# AINx2.net
KiCad netlist of a schematic drawn in EAGLE
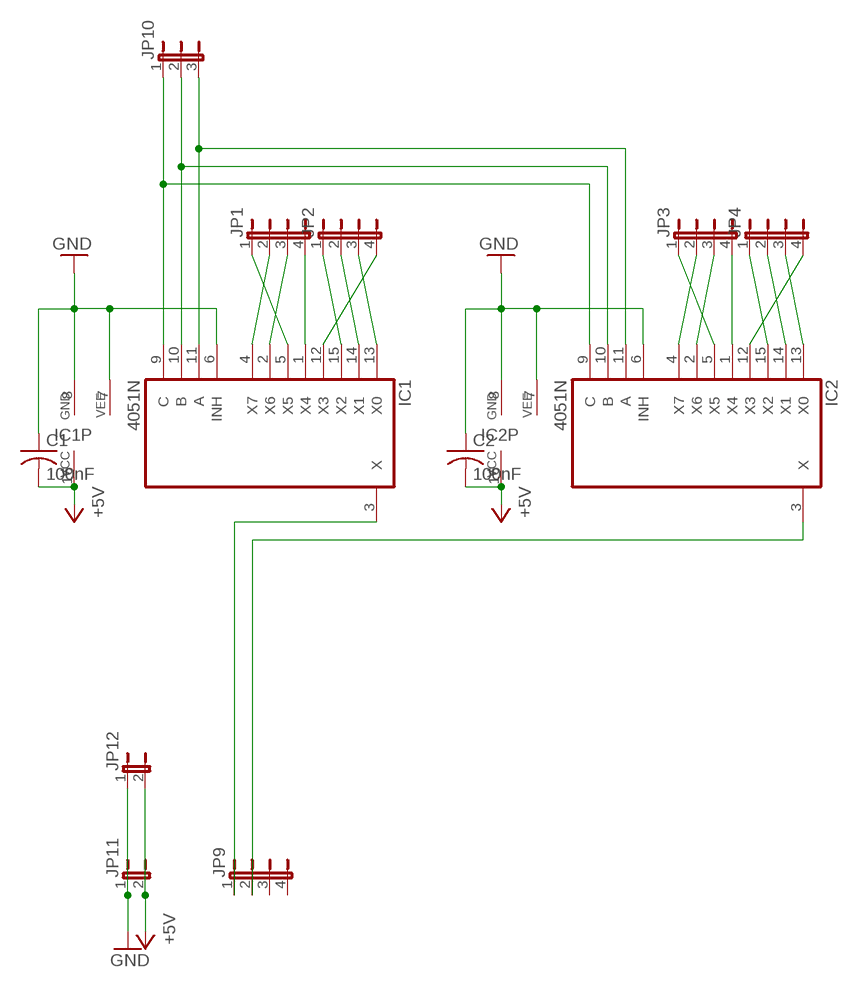
[diagram p0: schematic, sheet 1]

(export (version "E")
  (design (tool "Eeschema 10.0.6"))
  (components
    (comp (ref "C1")
      (value "100nF")
      (footprint "eagle-import:C025-025X050")
      (libsource (lib "eagle-import") (part "C-US025-025X050"))
    )
    (comp (ref "C2")
      (value "100nF")
      (footprint "eagle-import:C025-025X050")
      (libsource (lib "eagle-import") (part "C-US025-025X050"))
    )
    (comp (ref "IC1")
      (value "4051N")
      (footprint "eagle-import:DIL16")
      (libsource (lib "eagle-import") (part "4051N"))
    )
    (comp (ref "IC2")
      (value "4051N")
      (footprint "eagle-import:DIL16")
      (libsource (lib "eagle-import") (part "4051N"))
    )
    (comp (ref "JP1")
      (value "JP4E")
      (footprint "eagle-import:JP4")
      (libsource (lib "eagle-import") (part "JP4E"))
    )
    (comp (ref "JP2")
      (value "JP4E")
      (footprint "eagle-import:JP4")
      (libsource (lib "eagle-import") (part "JP4E"))
    )
    (comp (ref "JP3")
      (value "JP4E")
      (footprint "eagle-import:JP4")
      (libsource (lib "eagle-import") (part "JP4E"))
    )
    (comp (ref "JP4")
      (value "JP4E")
      (footprint "eagle-import:JP4")
      (libsource (lib "eagle-import") (part "JP4E"))
    )
    (comp (ref "JP9")
      (value "JP4E")
      (footprint "eagle-import:JP4")
      (libsource (lib "eagle-import") (part "JP4E"))
    )
    (comp (ref "JP10")
      (value "JP2E")
      (footprint "eagle-import:JP2")
      (libsource (lib "eagle-import") (part "JP2E"))
    )
    (comp (ref "JP11")
      (value "JP1E")
      (footprint "eagle-import:JP1")
      (libsource (lib "eagle-import") (part "JP1E"))
    )
    (comp (ref "JP12")
      (value "JP1E")
      (footprint "eagle-import:JP1")
      (libsource (lib "eagle-import") (part "JP1E"))
    )
  )
  (nets
    (net (code "1") (name "+5V") (class "Default")
      (node (ref "C1") (pin "2") (pinfunction "2_2") (pintype "passive"))
      (node (ref "C2") (pin "2") (pinfunction "2_2") (pintype "passive"))
      (node (ref "IC1") (pin "16") (pinfunction "VCC_16") (pintype "power_in"))
      (node (ref "IC2") (pin "16") (pinfunction "VCC_16") (pintype "power_in"))
      (node (ref "JP11") (pin "2") (pinfunction "2_2") (pintype "passive"))
      (node (ref "JP12") (pin "2") (pinfunction "2_2") (pintype "passive"))
    )
    (net (code "2") (name "GND") (class "Default")
      (node (ref "C1") (pin "1") (pinfunction "1_1") (pintype "passive"))
      (node (ref "C2") (pin "1") (pinfunction "1_1") (pintype "passive"))
      (node (ref "IC1") (pin "6") (pinfunction "INH_6") (pintype "input"))
      (node (ref "IC1") (pin "7") (pinfunction "VEE_7") (pintype "power_in"))
      (node (ref "IC1") (pin "8") (pinfunction "GND_8") (pintype "power_in"))
      (node (ref "IC2") (pin "6") (pinfunction "INH_6") (pintype "input"))
      (node (ref "IC2") (pin "7") (pinfunction "VEE_7") (pintype "power_in"))
      (node (ref "IC2") (pin "8") (pinfunction "GND_8") (pintype "power_in"))
      (node (ref "JP11") (pin "1") (pinfunction "1_1") (pintype "passive"))
      (node (ref "JP12") (pin "1") (pinfunction "1_1") (pintype "passive"))
    )
    (net (code "3") (name "Net-(IC1A-A)") (class "Default")
      (node (ref "IC1") (pin "11") (pinfunction "A_11") (pintype "input"))
      (node (ref "IC2") (pin "11") (pinfunction "A_11") (pintype "input"))
      (node (ref "JP10") (pin "3") (pinfunction "3_3") (pintype "passive"))
    )
    (net (code "4") (name "Net-(IC1A-B)") (class "Default")
      (node (ref "IC1") (pin "10") (pinfunction "B_10") (pintype "input"))
      (node (ref "IC2") (pin "10") (pinfunction "B_10") (pintype "input"))
      (node (ref "JP10") (pin "2") (pinfunction "2_2") (pintype "passive"))
    )
    (net (code "5") (name "Net-(IC1A-C)") (class "Default")
      (node (ref "IC1") (pin "9") (pinfunction "C_9") (pintype "input"))
      (node (ref "IC2") (pin "9") (pinfunction "C_9") (pintype "input"))
      (node (ref "JP10") (pin "1") (pinfunction "1_1") (pintype "passive"))
    )
    (net (code "6") (name "Net-(IC1A-X)") (class "Default")
      (node (ref "IC1") (pin "3") (pinfunction "X_3") (pintype "bidirectional"))
      (node (ref "JP9") (pin "1") (pinfunction "1_1") (pintype "passive"))
    )
    (net (code "7") (name "Net-(IC1A-X0)") (class "Default")
      (node (ref "IC1") (pin "13") (pinfunction "X0_13") (pintype "bidirectional"))
      (node (ref "JP2") (pin "3") (pinfunction "3_3") (pintype "passive"))
    )
    (net (code "8") (name "Net-(IC1A-X1)") (class "Default")
      (node (ref "IC1") (pin "14") (pinfunction "X1_14") (pintype "bidirectional"))
      (node (ref "JP2") (pin "2") (pinfunction "2_2") (pintype "passive"))
    )
    (net (code "9") (name "Net-(IC1A-X2)") (class "Default")
      (node (ref "IC1") (pin "15") (pinfunction "X2_15") (pintype "bidirectional"))
      (node (ref "JP2") (pin "1") (pinfunction "1_1") (pintype "passive"))
    )
    (net (code "10") (name "Net-(IC1A-X3)") (class "Default")
      (node (ref "IC1") (pin "12") (pinfunction "X3_12") (pintype "bidirectional"))
      (node (ref "JP2") (pin "4") (pinfunction "4_4") (pintype "passive"))
    )
    (net (code "11") (name "Net-(IC1A-X4)") (class "Default")
      (node (ref "IC1") (pin "1") (pinfunction "X4_1") (pintype "bidirectional"))
      (node (ref "JP1") (pin "4") (pinfunction "4_4") (pintype "passive"))
    )
    (net (code "12") (name "Net-(IC1A-X5)") (class "Default")
      (node (ref "IC1") (pin "5") (pinfunction "X5_5") (pintype "bidirectional"))
      (node (ref "JP1") (pin "1") (pinfunction "1_1") (pintype "passive"))
    )
    (net (code "13") (name "Net-(IC1A-X6)") (class "Default")
      (node (ref "IC1") (pin "2") (pinfunction "X6_2") (pintype "bidirectional"))
      (node (ref "JP1") (pin "3") (pinfunction "3_3") (pintype "passive"))
    )
    (net (code "14") (name "Net-(IC1A-X7)") (class "Default")
      (node (ref "IC1") (pin "4") (pinfunction "X7_4") (pintype "bidirectional"))
      (node (ref "JP1") (pin "2") (pinfunction "2_2") (pintype "passive"))
    )
    (net (code "15") (name "Net-(IC2A-X)") (class "Default")
      (node (ref "IC2") (pin "3") (pinfunction "X_3") (pintype "bidirectional"))
      (node (ref "JP9") (pin "2") (pinfunction "2_2") (pintype "passive"))
    )
    (net (code "16") (name "Net-(IC2A-X0)") (class "Default")
      (node (ref "IC2") (pin "13") (pinfunction "X0_13") (pintype "bidirectional"))
      (node (ref "JP4") (pin "3") (pinfunction "3_3") (pintype "passive"))
    )
    (net (code "17") (name "Net-(IC2A-X1)") (class "Default")
      (node (ref "IC2") (pin "14") (pinfunction "X1_14") (pintype "bidirectional"))
      (node (ref "JP4") (pin "2") (pinfunction "2_2") (pintype "passive"))
    )
    (net (code "18") (name "Net-(IC2A-X2)") (class "Default")
      (node (ref "IC2") (pin "15") (pinfunction "X2_15") (pintype "bidirectional"))
      (node (ref "JP4") (pin "1") (pinfunction "1_1") (pintype "passive"))
    )
    (net (code "19") (name "Net-(IC2A-X3)") (class "Default")
      (node (ref "IC2") (pin "12") (pinfunction "X3_12") (pintype "bidirectional"))
      (node (ref "JP4") (pin "4") (pinfunction "4_4") (pintype "passive"))
    )
    (net (code "20") (name "Net-(IC2A-X4)") (class "Default")
      (node (ref "IC2") (pin "1") (pinfunction "X4_1") (pintype "bidirectional"))
      (node (ref "JP3") (pin "4") (pinfunction "4_4") (pintype "passive"))
    )
    (net (code "21") (name "Net-(IC2A-X5)") (class "Default")
      (node (ref "IC2") (pin "5") (pinfunction "X5_5") (pintype "bidirectional"))
      (node (ref "JP3") (pin "1") (pinfunction "1_1") (pintype "passive"))
    )
    (net (code "22") (name "Net-(IC2A-X6)") (class "Default")
      (node (ref "IC2") (pin "2") (pinfunction "X6_2") (pintype "bidirectional"))
      (node (ref "JP3") (pin "3") (pinfunction "3_3") (pintype "passive"))
    )
    (net (code "23") (name "Net-(IC2A-X7)") (class "Default")
      (node (ref "IC2") (pin "4") (pinfunction "X7_4") (pintype "bidirectional"))
      (node (ref "JP3") (pin "2") (pinfunction "2_2") (pintype "passive"))
    )
    (net (code "24") (name "unconnected-(JP9-Pad3)") (class "Default")
      (node (ref "JP9") (pin "3") (pinfunction "3_3") (pintype "passive"))
    )
    (net (code "25") (name "unconnected-(JP9-Pad4)") (class "Default")
      (node (ref "JP9") (pin "4") (pinfunction "4_4") (pintype "passive"))
    )
  )
)
